# MAZ000153_-_Diagrama_el_ctrico.net
KiCad netlist of a schematic drawn in Altium Designer
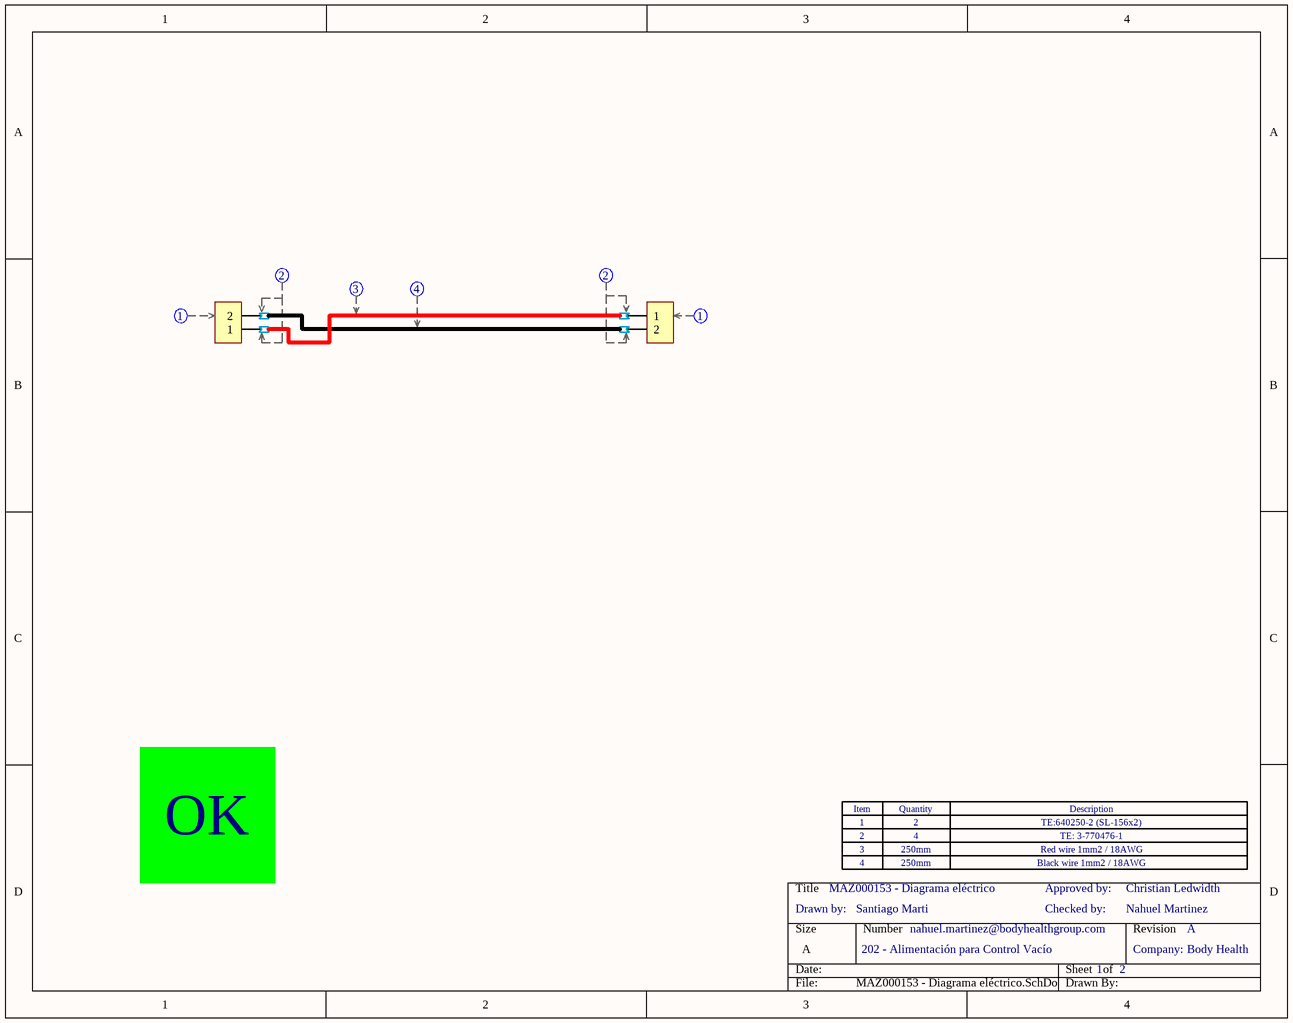
[diagram p0: MAZ000153 - Diagrama eléctrico.SchDoc]

(export (version "E")
  (design (tool "Eeschema 10.0.6"))
  (components
    (comp (ref "Con1")
      (value "SL156-2")
      (description "CONN RECEPT 2 POS W/RAMP SL-156")
      (libsource (lib "") (part "SL156-2_2"))
    )
    (comp (ref "Con2")
      (value "SL156-2")
      (description "CONN RECEPT 2 POS W/RAMP SL-156")
      (libsource (lib "") (part "SL156-2_2"))
    )
    (comp (ref "Soc1")
      (value "sock_SL156_770476-1")
      (description "CONN SOCKET 18-24AWG CRIMP TIN")
      (libsource (lib "LibreriaParaPlanos") (part "sock_SL156_770476-1"))
    )
    (comp (ref "Soc2")
      (value "sock_SL156_770476-1")
      (description "CONN SOCKET 18-24AWG CRIMP TIN")
      (libsource (lib "LibreriaParaPlanos") (part "sock_SL156_770476-1"))
    )
    (comp (ref "Soc3")
      (value "sock_SL156_770476-1")
      (description "CONN SOCKET 18-24AWG CRIMP TIN")
      (libsource (lib "LibreriaParaPlanos") (part "sock_SL156_770476-1"))
    )
    (comp (ref "Soc4")
      (value "sock_SL156_770476-1")
      (description "CONN SOCKET 18-24AWG CRIMP TIN")
      (libsource (lib "LibreriaParaPlanos") (part "sock_SL156_770476-1"))
    )
    (comp (ref "Zoc1")
      (value "Zócalo_Header")
      (description "Header para el zócalo de referencias")
      (libsource (lib "LibreriaParaPlanos") (part "Zócalo_Header"))
    )
    (comp (ref "Zoc2")
      (value "Zócalo_Item")
      (description "Ítem para el zócalo de referencias")
      (libsource (lib "LibreriaParaPlanos") (part "Zócalo_Item"))
    )
    (comp (ref "Zoc3")
      (value "Zócalo_Item")
      (description "Ítem para el zócalo de referencias")
      (libsource (lib "LibreriaParaPlanos") (part "Zócalo_Item"))
    )
    (comp (ref "Zoc4")
      (value "Zócalo_Item")
      (description "Ítem para el zócalo de referencias")
      (libsource (lib "LibreriaParaPlanos") (part "Zócalo_Item"))
    )
    (comp (ref "Zoc5")
      (value "Zócalo_Item")
      (description "Ítem para el zócalo de referencias")
      (libsource (lib "LibreriaParaPlanos") (part "Zócalo_Item"))
    )
  )
  (nets
    (net (code "1") (name "Net-(Con1-Pad1)") (class "Default")
      (node (ref "Con1") (pin "1") (pinfunction "1_1") (pintype "passive"))
      (node (ref "Soc3") (pin "0") (pinfunction "0_0") (pintype "passive"))
    )
    (net (code "2") (name "Net-(Con1-Pad2)") (class "Default")
      (node (ref "Con1") (pin "2") (pinfunction "2_2") (pintype "passive"))
      (node (ref "Soc1") (pin "0") (pinfunction "0_0") (pintype "passive"))
    )
    (net (code "3") (name "Net-(Con2-Pad1)") (class "Default")
      (node (ref "Con2") (pin "1") (pinfunction "1_1") (pintype "passive"))
      (node (ref "Soc2") (pin "0") (pinfunction "0_0") (pintype "passive"))
    )
    (net (code "4") (name "Net-(Con2-Pad2)") (class "Default")
      (node (ref "Con2") (pin "2") (pinfunction "2_2") (pintype "passive"))
      (node (ref "Soc4") (pin "0") (pinfunction "0_0") (pintype "passive"))
    )
    (net (code "5") (name "Net-(Soc1-Pad1)") (class "Default")
      (node (ref "Soc1") (pin "1") (pinfunction "1_1") (pintype "passive"))
      (node (ref "Soc4") (pin "1") (pinfunction "1_1") (pintype "passive"))
    )
    (net (code "6") (name "Net-(Soc2-Pad1)") (class "Default")
      (node (ref "Soc2") (pin "1") (pinfunction "1_1") (pintype "passive"))
      (node (ref "Soc3") (pin "1") (pinfunction "1_1") (pintype "passive"))
    )
  )
)
